# Squirco_Logic_v1_0.net
KiCad netlist of a schematic drawn in EAGLE
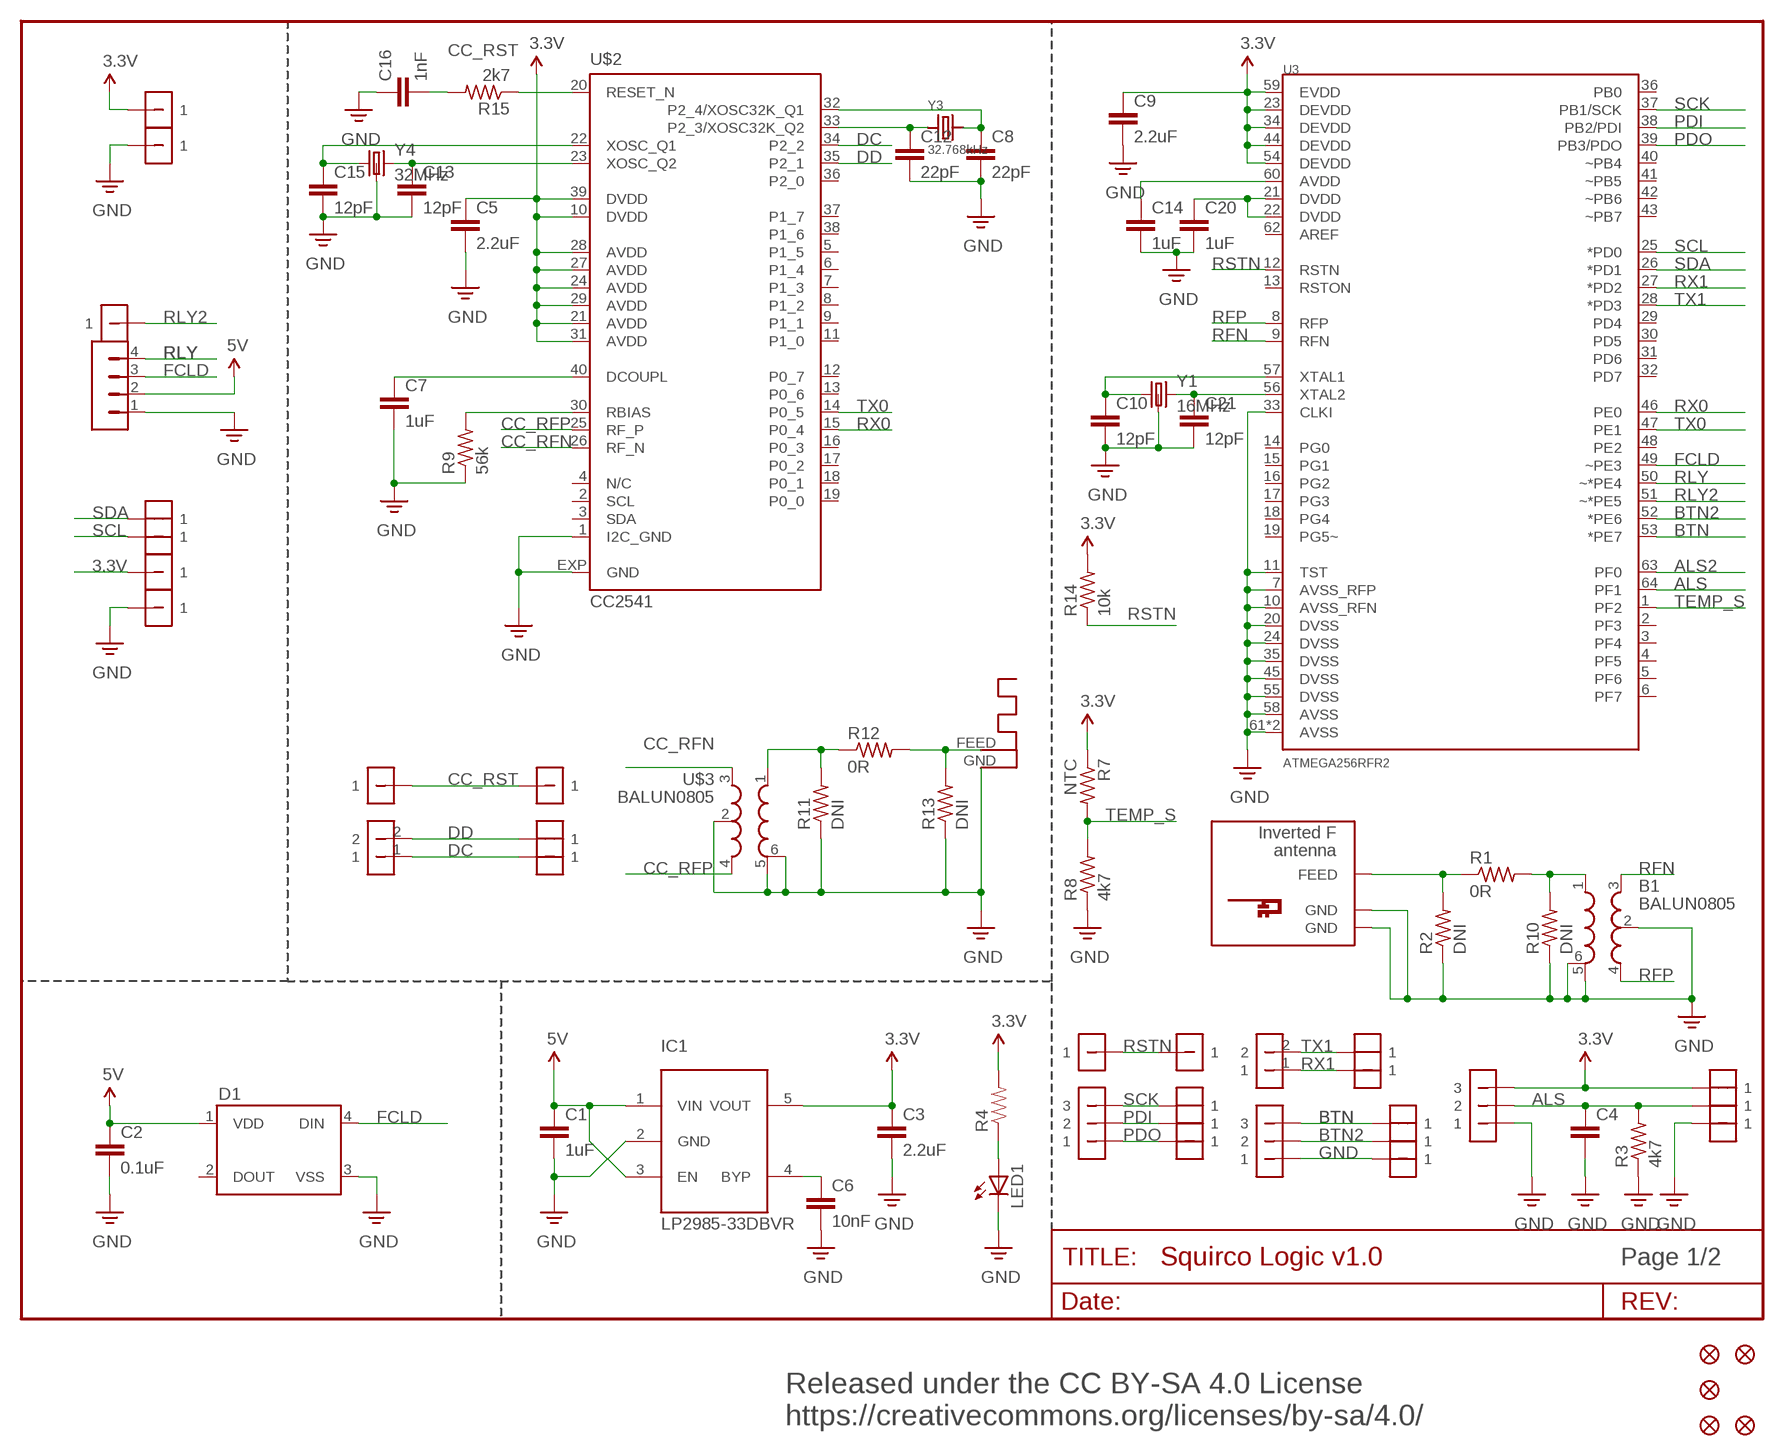
[diagram p0: schematic, sheet 1]

(export (version "E")
  (design (tool "Eeschema 10.0.6"))
  (components
    (comp (ref "ANT1")
      (value "ANTENNA")
      (footprint "eagle-import:RN-ANT")
      (libsource (lib "eagle-import") (part "ANTENNA"))
    )
    (comp (ref "B1")
      (value "BALUN0805")
      (footprint "eagle-import:BALUN-2-4GHZ")
      (libsource (lib "eagle-import") (part "BALUN0805"))
    )
    (comp (ref "C1")
      (value "1uF")
      (footprint "eagle-import:0603-CAP")
      (libsource (lib "eagle-import") (part "CAP0603-CAP"))
    )
    (comp (ref "C2")
      (value "0.1uF")
      (footprint "eagle-import:0603-CAP")
      (libsource (lib "eagle-import") (part "CAP0603-CAP"))
    )
    (comp (ref "C3")
      (value "2.2uF")
      (footprint "eagle-import:0603-CAP")
      (libsource (lib "eagle-import") (part "CAP0603-CAP"))
    )
    (comp (ref "C4")
      (value "CAP0603-CAP")
      (footprint "eagle-import:0603-CAP")
      (libsource (lib "eagle-import") (part "CAP0603-CAP"))
    )
    (comp (ref "C5")
      (value "2.2uF")
      (footprint "eagle-import:0603-CAP")
      (libsource (lib "eagle-import") (part "CAP0603-CAP"))
    )
    (comp (ref "C6")
      (value "10nF")
      (footprint "eagle-import:0603-CAP")
      (libsource (lib "eagle-import") (part "CAP0603-CAP"))
    )
    (comp (ref "C7")
      (value "1uF")
      (footprint "eagle-import:0603-CAP")
      (libsource (lib "eagle-import") (part "CAP0603-CAP"))
    )
    (comp (ref "C8")
      (value "22pF")
      (footprint "eagle-import:0402-CAP")
      (libsource (lib "eagle-import") (part "CAP0402-CAP"))
    )
    (comp (ref "C9")
      (value "2.2uF")
      (footprint "eagle-import:0603-CAP")
      (libsource (lib "eagle-import") (part "CAP0603-CAP"))
    )
    (comp (ref "C10")
      (value "12pF")
      (footprint "eagle-import:0402-CAP")
      (libsource (lib "eagle-import") (part "CAP0402-CAP"))
    )
    (comp (ref "C12")
      (value "22pF")
      (footprint "eagle-import:0402-CAP")
      (libsource (lib "eagle-import") (part "CAP0402-CAP"))
    )
    (comp (ref "C13")
      (value "12pF")
      (footprint "eagle-import:0402-CAP")
      (libsource (lib "eagle-import") (part "CAP0402-CAP"))
    )
    (comp (ref "C14")
      (value "1uF")
      (footprint "eagle-import:0603-CAP")
      (libsource (lib "eagle-import") (part "CAP0603-CAP"))
    )
    (comp (ref "C15")
      (value "12pF")
      (footprint "eagle-import:0402-CAP")
      (libsource (lib "eagle-import") (part "CAP0402-CAP"))
    )
    (comp (ref "C16")
      (value "1nF")
      (footprint "eagle-import:0603-CAP")
      (libsource (lib "eagle-import") (part "CAP0603-CAP"))
    )
    (comp (ref "C20")
      (value "1uF")
      (footprint "eagle-import:0603-CAP")
      (libsource (lib "eagle-import") (part "CAP0603-CAP"))
    )
    (comp (ref "C21")
      (value "12pF")
      (footprint "eagle-import:0402-CAP")
      (libsource (lib "eagle-import") (part "CAP0402-CAP"))
    )
    (comp (ref "D1")
      (value "WS2812B")
      (footprint "eagle-import:WS2812B")
      (libsource (lib "eagle-import") (part "WS2812B"))
    )
    (comp (ref "FID1")
      (value "FIDUCIALUFIDUCIAL")
      (footprint "eagle-import:MICRO-FIDUCIAL")
      (libsource (lib "eagle-import") (part "FIDUCIALUFIDUCIAL"))
    )
    (comp (ref "FID2")
      (value "FIDUCIALUFIDUCIAL")
      (footprint "eagle-import:MICRO-FIDUCIAL")
      (libsource (lib "eagle-import") (part "FIDUCIALUFIDUCIAL"))
    )
    (comp (ref "FID3")
      (value "FIDUCIALUFIDUCIAL")
      (footprint "eagle-import:MICRO-FIDUCIAL")
      (libsource (lib "eagle-import") (part "FIDUCIALUFIDUCIAL"))
    )
    (comp (ref "FID5")
      (value "FIDUCIALUFIDUCIAL")
      (footprint "eagle-import:MICRO-FIDUCIAL")
      (libsource (lib "eagle-import") (part "FIDUCIALUFIDUCIAL"))
    )
    (comp (ref "FID6")
      (value "FIDUCIALUFIDUCIAL")
      (footprint "eagle-import:MICRO-FIDUCIAL")
      (libsource (lib "eagle-import") (part "FIDUCIALUFIDUCIAL"))
    )
    (comp (ref "IC1")
      (value "LP2985-33DBVR")
      (footprint "eagle-import:SOT23-5L")
      (libsource (lib "eagle-import") (part "LP298XS"))
    )
    (comp (ref "JP1")
      (value "M02")
      (footprint "eagle-import:M02")
      (libsource (lib "eagle-import") (part "M02"))
    )
    (comp (ref "LED1")
      (value "LEDCHIP-LED0805")
      (footprint "eagle-import:CHIP-LED0805")
      (libsource (lib "eagle-import") (part "LEDCHIP-LED0805"))
    )
    (comp (ref "R1")
      (value "0R")
      (footprint "eagle-import:R0402")
      (libsource (lib "eagle-import") (part "R-US_R0402"))
    )
    (comp (ref "R2")
      (value "DNI")
      (footprint "eagle-import:R0402")
      (libsource (lib "eagle-import") (part "R-US_R0402"))
    )
    (comp (ref "R3")
      (value "4k7")
      (footprint "eagle-import:R0603")
      (libsource (lib "eagle-import") (part "R-US_R0603"))
    )
    (comp (ref "R4")
      (value "RESISTOR0603")
      (footprint "eagle-import:0603-RES")
      (libsource (lib "eagle-import") (part "RESISTOR0603"))
    )
    (comp (ref "R7")
      (value "NTC")
      (footprint "eagle-import:R0402")
      (libsource (lib "eagle-import") (part "R-US_R0402"))
    )
    (comp (ref "R8")
      (value "4k7")
      (footprint "eagle-import:R0603")
      (libsource (lib "eagle-import") (part "R-US_R0603"))
    )
    (comp (ref "R9")
      (value "56k")
      (footprint "eagle-import:R0603")
      (libsource (lib "eagle-import") (part "R-US_R0603"))
    )
    (comp (ref "R10")
      (value "DNI")
      (footprint "eagle-import:R0402")
      (libsource (lib "eagle-import") (part "R-US_R0402"))
    )
    (comp (ref "R11")
      (value "DNI")
      (footprint "eagle-import:R0402")
      (libsource (lib "eagle-import") (part "R-US_R0402"))
    )
    (comp (ref "R12")
      (value "0R")
      (footprint "eagle-import:R0402")
      (libsource (lib "eagle-import") (part "R-US_R0402"))
    )
    (comp (ref "R13")
      (value "DNI")
      (footprint "eagle-import:R0402")
      (libsource (lib "eagle-import") (part "R-US_R0402"))
    )
    (comp (ref "R14")
      (value "10k")
      (footprint "eagle-import:R0603")
      (libsource (lib "eagle-import") (part "R-US_R0603"))
    )
    (comp (ref "R15")
      (value "2k7")
      (footprint "eagle-import:R0603")
      (libsource (lib "eagle-import") (part "R-US_R0603"))
    )
    (comp (ref "U$1")
      (value "INVERTED_F_ANTENNA+5")
      (footprint "eagle-import:DN007+5")
      (libsource (lib "eagle-import") (part "INVERTED_F_ANTENNA+5"))
    )
    (comp (ref "U$2")
      (value "CC2541")
      (footprint "eagle-import:RHA_S-PVQFN-N40")
      (libsource (lib "eagle-import") (part "CC2541"))
    )
    (comp (ref "U$3")
      (value "BALUN0805")
      (footprint "eagle-import:BALUN-2-4GHZ")
      (libsource (lib "eagle-import") (part "BALUN0805"))
    )
    (comp (ref "U$4")
      (value "M03")
      (footprint "eagle-import:M03")
      (libsource (lib "eagle-import") (part "M03"))
    )
    (comp (ref "U$5")
      (value "S04-4MM")
      (footprint "eagle-import:S04-4MM")
      (libsource (lib "eagle-import") (part "S04-4MM"))
    )
    (comp (ref "U$6")
      (value "M03")
      (footprint "eagle-import:M03")
      (libsource (lib "eagle-import") (part "M03"))
    )
    (comp (ref "U$7")
      (value "M01")
      (footprint "eagle-import:M01")
      (libsource (lib "eagle-import") (part "M01"))
    )
    (comp (ref "U$8")
      (value "M01")
      (footprint "eagle-import:M01")
      (libsource (lib "eagle-import") (part "M01"))
    )
    (comp (ref "U$9")
      (value "M02")
      (footprint "eagle-import:M02")
      (libsource (lib "eagle-import") (part "M02"))
    )
    (comp (ref "U$10")
      (value "S01C-4MM")
      (footprint "eagle-import:S01C-4MM")
      (libsource (lib "eagle-import") (part "S01C-4MM"))
    )
    (comp (ref "U$11")
      (value "S01C-4MM")
      (footprint "eagle-import:S01C-4MM")
      (libsource (lib "eagle-import") (part "S01C-4MM"))
    )
    (comp (ref "U$12")
      (value "S01C-4MM")
      (footprint "eagle-import:S01C-4MM")
      (libsource (lib "eagle-import") (part "S01C-4MM"))
    )
    (comp (ref "U$13")
      (value "S01C-4MM")
      (footprint "eagle-import:S01C-4MM")
      (libsource (lib "eagle-import") (part "S01C-4MM"))
    )
    (comp (ref "U$14")
      (value "S01C-4MM")
      (footprint "eagle-import:S01C-4MM")
      (libsource (lib "eagle-import") (part "S01C-4MM"))
    )
    (comp (ref "U$15")
      (value "S01C-4MM")
      (footprint "eagle-import:S01C-4MM")
      (libsource (lib "eagle-import") (part "S01C-4MM"))
    )
    (comp (ref "U$16")
      (value "S01C-4MM")
      (footprint "eagle-import:S01C-4MM")
      (libsource (lib "eagle-import") (part "S01C-4MM"))
    )
    (comp (ref "U$17")
      (value "S01C-4MM")
      (footprint "eagle-import:S01C-4MM")
      (libsource (lib "eagle-import") (part "S01C-4MM"))
    )
    (comp (ref "U$18")
      (value "S01C-4MM")
      (footprint "eagle-import:S01C-4MM")
      (libsource (lib "eagle-import") (part "S01C-4MM"))
    )
    (comp (ref "U$19")
      (value "S01C-4MM")
      (footprint "eagle-import:S01C-4MM")
      (libsource (lib "eagle-import") (part "S01C-4MM"))
    )
    (comp (ref "U$20")
      (value "S01C-4MM")
      (footprint "eagle-import:S01C-4MM")
      (libsource (lib "eagle-import") (part "S01C-4MM"))
    )
    (comp (ref "U$21")
      (value "S01C-4MM")
      (footprint "eagle-import:S01C-4MM")
      (libsource (lib "eagle-import") (part "S01C-4MM"))
    )
    (comp (ref "U$22")
      (value "S01C-4MM")
      (footprint "eagle-import:S01C-4MM")
      (libsource (lib "eagle-import") (part "S01C-4MM"))
    )
    (comp (ref "U$23")
      (value "S01C-4MM")
      (footprint "eagle-import:S01C-4MM")
      (libsource (lib "eagle-import") (part "S01C-4MM"))
    )
    (comp (ref "U$24")
      (value "S01C-4MM")
      (footprint "eagle-import:S01C-4MM")
      (libsource (lib "eagle-import") (part "S01C-4MM"))
    )
    (comp (ref "U$25")
      (value "M03")
      (footprint "eagle-import:M03")
      (libsource (lib "eagle-import") (part "M03"))
    )
    (comp (ref "U$26")
      (value "S01C-4MM")
      (footprint "eagle-import:S01C-4MM")
      (libsource (lib "eagle-import") (part "S01C-4MM"))
    )
    (comp (ref "U$27")
      (value "S01C-4MM")
      (footprint "eagle-import:S01C-4MM")
      (libsource (lib "eagle-import") (part "S01C-4MM"))
    )
    (comp (ref "U$30")
      (value "S01C-4MM")
      (footprint "eagle-import:S01C-4MM")
      (libsource (lib "eagle-import") (part "S01C-4MM"))
    )
    (comp (ref "U$31")
      (value "S01C-4MM")
      (footprint "eagle-import:S01C-4MM")
      (libsource (lib "eagle-import") (part "S01C-4MM"))
    )
    (comp (ref "U$32")
      (value "S01-4MM")
      (footprint "eagle-import:S01-4MM")
      (libsource (lib "eagle-import") (part "S01-4MM"))
    )
    (comp (ref "U$33")
      (value "S01-4MM")
      (footprint "eagle-import:S01-4MM")
      (libsource (lib "eagle-import") (part "S01-4MM"))
    )
    (comp (ref "U$34")
      (value "S01C-4MM")
      (footprint "eagle-import:S01C-4MM")
      (libsource (lib "eagle-import") (part "S01C-4MM"))
    )
    (comp (ref "U3")
      (value "ATMEGA256RFR2")
      (footprint "eagle-import:QFN-64")
      (libsource (lib "eagle-import") (part "ATMEGA256RFR2"))
    )
    (comp (ref "Y1")
      (value "16MHz")
      (footprint "eagle-import:CRYSTAL-SMD-2.5X2-ABM10")
      (libsource (lib "eagle-import") (part "CRYSTALABM10"))
    )
    (comp (ref "Y3")
      (value "32.768kHz")
      (footprint "eagle-import:ABS07")
      (libsource (lib "eagle-import") (part "CRYSTAL.ABS07"))
    )
    (comp (ref "Y4")
      (value "32MHz")
      (footprint "eagle-import:CRYSTAL-SMD-2.5X2-ABM10")
      (libsource (lib "eagle-import") (part "CRYSTALABM10"))
    )
  )
  (nets
    (net (code "1") (name "/ALS") (class "Default")
      (node (ref "C4") (pin "1") (pinfunction "1_1") (pintype "passive"))
      (node (ref "R3") (pin "2") (pinfunction "2_2") (pintype "passive"))
      (node (ref "U$25") (pin "2") (pinfunction "2_2") (pintype "bidirectional"))
      (node (ref "U$31") (pin "P$1") (pinfunction "1_P$1") (pintype "bidirectional"))
      (node (ref "U3") (pin "64") (pinfunction "PF1_64") (pintype "bidirectional"))
    )
    (net (code "2") (name "/ALS2") (class "Default")
      (node (ref "U3") (pin "63") (pinfunction "PF0_63") (pintype "bidirectional"))
    )
    (net (code "3") (name "/BTN") (class "Default")
      (node (ref "U$22") (pin "P$1") (pinfunction "1_P$1") (pintype "bidirectional"))
      (node (ref "U$6") (pin "3") (pinfunction "3_3") (pintype "bidirectional"))
      (node (ref "U3") (pin "53") (pinfunction "*PE7_53") (pintype "bidirectional"))
    )
    (net (code "4") (name "/BTN2") (class "Default")
      (node (ref "U$23") (pin "P$1") (pinfunction "1_P$1") (pintype "bidirectional"))
      (node (ref "U$6") (pin "2") (pinfunction "2_2") (pintype "bidirectional"))
      (node (ref "U3") (pin "52") (pinfunction "*PE6_52") (pintype "bidirectional"))
    )
    (net (code "5") (name "/CC_RFN") (class "Default")
      (node (ref "U$2") (pin "26") (pinfunction "RF_N_26") (pintype "bidirectional"))
      (node (ref "U$3") (pin "3") (pinfunction "3_3") (pintype "bidirectional"))
    )
    (net (code "6") (name "/CC_RFP") (class "Default")
      (node (ref "U$2") (pin "25") (pinfunction "RF_P_25") (pintype "bidirectional"))
      (node (ref "U$3") (pin "4") (pinfunction "4_4") (pintype "bidirectional"))
    )
    (net (code "7") (name "/CC_RST") (class "Default")
      (node (ref "C16") (pin "2") (pinfunction "2_2") (pintype "passive"))
      (node (ref "R15") (pin "2") (pinfunction "2_2") (pintype "passive"))
      (node (ref "U$17") (pin "P$1") (pinfunction "1_P$1") (pintype "bidirectional"))
      (node (ref "U$8") (pin "1") (pinfunction "1_1") (pintype "bidirectional"))
    )
    (net (code "8") (name "/DC") (class "Default")
      (node (ref "U$19") (pin "P$1") (pinfunction "1_P$1") (pintype "bidirectional"))
      (node (ref "U$2") (pin "34") (pinfunction "P2_2_34") (pintype "bidirectional"))
      (node (ref "U$9") (pin "1") (pinfunction "1_1") (pintype "bidirectional"))
    )
    (net (code "9") (name "/DD") (class "Default")
      (node (ref "U$18") (pin "P$1") (pinfunction "1_P$1") (pintype "bidirectional"))
      (node (ref "U$2") (pin "35") (pinfunction "P2_1_35") (pintype "bidirectional"))
      (node (ref "U$9") (pin "2") (pinfunction "2_2") (pintype "bidirectional"))
    )
    (net (code "10") (name "/FCLD") (class "Default")
      (node (ref "D1") (pin "4") (pinfunction "DIN_4") (pintype "input"))
      (node (ref "U$5") (pin "3") (pinfunction "3_3") (pintype "bidirectional"))
      (node (ref "U3") (pin "49") (pinfunction "~{PE3}_49") (pintype "bidirectional"))
    )
    (net (code "11") (name "/N{slash}C") (class "Default")
      (node (ref "U$2") (pin "4") (pinfunction "N/C_4") (pintype "power_in"))
    )
    (net (code "12") (name "/PDI") (class "Default")
      (node (ref "U$13") (pin "P$1") (pinfunction "1_P$1") (pintype "bidirectional"))
      (node (ref "U$4") (pin "2") (pinfunction "2_2") (pintype "bidirectional"))
      (node (ref "U3") (pin "38") (pinfunction "PB2/PDI_38") (pintype "bidirectional"))
    )
    (net (code "13") (name "/PDO") (class "Default")
      (node (ref "U$14") (pin "P$1") (pinfunction "1_P$1") (pintype "bidirectional"))
      (node (ref "U$4") (pin "1") (pinfunction "1_1") (pintype "bidirectional"))
      (node (ref "U3") (pin "39") (pinfunction "PB3/PDO_39") (pintype "bidirectional"))
    )
    (net (code "14") (name "/RFN") (class "Default")
      (node (ref "B1") (pin "3") (pinfunction "3_3") (pintype "bidirectional"))
      (node (ref "U3") (pin "9") (pinfunction "RFN_9") (pintype "bidirectional"))
    )
    (net (code "15") (name "/RFP") (class "Default")
      (node (ref "B1") (pin "4") (pinfunction "4_4") (pintype "bidirectional"))
      (node (ref "U3") (pin "8") (pinfunction "RFP_8") (pintype "bidirectional"))
    )
    (net (code "16") (name "/RLY") (class "Default")
      (node (ref "U$5") (pin "4") (pinfunction "4_4") (pintype "bidirectional"))
      (node (ref "U3") (pin "50") (pinfunction "~{*PE4}_50") (pintype "bidirectional"))
    )
    (net (code "17") (name "/RLY2") (class "Default")
      (node (ref "U$34") (pin "P$1") (pinfunction "1_P$1") (pintype "bidirectional"))
      (node (ref "U3") (pin "51") (pinfunction "~{*PE5}_51") (pintype "bidirectional"))
    )
    (net (code "18") (name "/RSTN") (class "Default")
      (node (ref "R14") (pin "1") (pinfunction "1_1") (pintype "passive"))
      (node (ref "U$11") (pin "P$1") (pinfunction "1_P$1") (pintype "bidirectional"))
      (node (ref "U$7") (pin "1") (pinfunction "1_1") (pintype "bidirectional"))
      (node (ref "U3") (pin "12") (pinfunction "RSTN_12") (pintype "bidirectional"))
    )
    (net (code "19") (name "/RX0") (class "Default")
      (node (ref "U$2") (pin "15") (pinfunction "P0_4_15") (pintype "bidirectional"))
      (node (ref "U3") (pin "46") (pinfunction "PE0_46") (pintype "bidirectional"))
    )
    (net (code "20") (name "/RX1") (class "Default")
      (node (ref "JP1") (pin "1") (pinfunction "1_1") (pintype "bidirectional"))
      (node (ref "U$16") (pin "P$1") (pinfunction "1_P$1") (pintype "bidirectional"))
      (node (ref "U3") (pin "27") (pinfunction "*PD2_27") (pintype "bidirectional"))
    )
    (net (code "21") (name "/SCK") (class "Default")
      (node (ref "U$12") (pin "P$1") (pinfunction "1_P$1") (pintype "bidirectional"))
      (node (ref "U$4") (pin "3") (pinfunction "3_3") (pintype "bidirectional"))
      (node (ref "U3") (pin "37") (pinfunction "PB1/SCK_37") (pintype "bidirectional"))
    )
    (net (code "22") (name "/SCL") (class "Default")
      (node (ref "U$24") (pin "P$1") (pinfunction "1_P$1") (pintype "bidirectional"))
      (node (ref "U3") (pin "25") (pinfunction "*PD0_25") (pintype "bidirectional"))
    )
    (net (code "23") (name "/SDA") (class "Default")
      (node (ref "U$10") (pin "P$1") (pinfunction "1_P$1") (pintype "bidirectional"))
      (node (ref "U3") (pin "26") (pinfunction "*PD1_26") (pintype "bidirectional"))
    )
    (net (code "24") (name "/TEMP_S") (class "Default")
      (node (ref "R7") (pin "2") (pinfunction "2_2") (pintype "passive"))
      (node (ref "R8") (pin "2") (pinfunction "2_2") (pintype "passive"))
      (node (ref "U3") (pin "1") (pinfunction "PF2_1") (pintype "bidirectional"))
    )
    (net (code "25") (name "/TX0") (class "Default")
      (node (ref "U$2") (pin "14") (pinfunction "P0_5_14") (pintype "bidirectional"))
      (node (ref "U3") (pin "47") (pinfunction "PE1_47") (pintype "bidirectional"))
    )
    (net (code "26") (name "/TX1") (class "Default")
      (node (ref "JP1") (pin "2") (pinfunction "2_2") (pintype "bidirectional"))
      (node (ref "U$15") (pin "P$1") (pinfunction "1_P$1") (pintype "bidirectional"))
      (node (ref "U3") (pin "28") (pinfunction "*PD3_28") (pintype "bidirectional"))
    )
    (net (code "27") (name "3.3V") (class "Default")
      (node (ref "C3") (pin "1") (pinfunction "1_1") (pintype "passive"))
      (node (ref "C5") (pin "1") (pinfunction "1_1") (pintype "passive"))
      (node (ref "C9") (pin "1") (pinfunction "1_1") (pintype "passive"))
      (node (ref "IC1") (pin "5") (pinfunction "VOUT_5") (pintype "bidirectional"))
      (node (ref "R14") (pin "2") (pinfunction "2_2") (pintype "passive"))
      (node (ref "R4") (pin "2") (pinfunction "2_2") (pintype "passive"))
      (node (ref "R7") (pin "1") (pinfunction "1_1") (pintype "passive"))
      (node (ref "U$2") (pin "10") (pinfunction "DVDD_10") (pintype "power_in"))
      (node (ref "U$2") (pin "21") (pinfunction "AVDD_21") (pintype "power_in"))
      (node (ref "U$2") (pin "24") (pinfunction "AVDD_24") (pintype "power_in"))
      (node (ref "U$2") (pin "27") (pinfunction "AVDD_27") (pintype "power_in"))
      (node (ref "U$2") (pin "28") (pinfunction "AVDD_28") (pintype "power_in"))
      (node (ref "U$2") (pin "29") (pinfunction "AVDD_29") (pintype "power_in"))
      (node (ref "U$2") (pin "31") (pinfunction "AVDD_31") (pintype "power_in"))
      (node (ref "U$2") (pin "39") (pinfunction "DVDD_39") (pintype "power_in"))
      (node (ref "U$20") (pin "P$1") (pinfunction "1_P$1") (pintype "bidirectional"))
      (node (ref "U$25") (pin "3") (pinfunction "3_3") (pintype "bidirectional"))
      (node (ref "U$26") (pin "P$1") (pinfunction "1_P$1") (pintype "bidirectional"))
      (node (ref "U$30") (pin "P$1") (pinfunction "1_P$1") (pintype "bidirectional"))
      (node (ref "U3") (pin "23") (pinfunction "DEVDD_23") (pintype "bidirectional"))
      (node (ref "U3") (pin "34") (pinfunction "DEVDD_34") (pintype "bidirectional"))
      (node (ref "U3") (pin "44") (pinfunction "DEVDD_44") (pintype "bidirectional"))
      (node (ref "U3") (pin "54") (pinfunction "DEVDD_54") (pintype "bidirectional"))
      (node (ref "U3") (pin "59") (pinfunction "EVDD_59") (pintype "bidirectional"))
    )
    (net (code "28") (name "5V") (class "Default")
      (node (ref "C1") (pin "1") (pinfunction "1_1") (pintype "passive"))
      (node (ref "C2") (pin "1") (pinfunction "1_1") (pintype "passive"))
      (node (ref "D1") (pin "1") (pinfunction "VDD_1") (pintype "power_in"))
      (node (ref "IC1") (pin "1") (pinfunction "VIN_1") (pintype "bidirectional"))
      (node (ref "IC1") (pin "3") (pinfunction "EN_3") (pintype "bidirectional"))
      (node (ref "U$5") (pin "2") (pinfunction "2_2") (pintype "bidirectional"))
    )
    (net (code "29") (name "GND") (class "Default")
      (node (ref "ANT1") (pin "GND") (pinfunction "GND_GND") (pintype "passive"))
      (node (ref "B1") (pin "2") (pinfunction "2_2") (pintype "bidirectional"))
      (node (ref "B1") (pin "5") (pinfunction "5_5") (pintype "bidirectional"))
      (node (ref "B1") (pin "6") (pinfunction "6_6") (pintype "bidirectional"))
      (node (ref "C1") (pin "2") (pinfunction "2_2") (pintype "passive"))
      (node (ref "C10") (pin "2") (pinfunction "2_2") (pintype "passive"))
      (node (ref "C12") (pin "2") (pinfunction "2_2") (pintype "passive"))
      (node (ref "C13") (pin "2") (pinfunction "2_2") (pintype "passive"))
      (node (ref "C14") (pin "2") (pinfunction "2_2") (pintype "passive"))
      (node (ref "C15") (pin "2") (pinfunction "2_2") (pintype "passive"))
      (node (ref "C16") (pin "1") (pinfunction "1_1") (pintype "passive"))
      (node (ref "C2") (pin "2") (pinfunction "2_2") (pintype "passive"))
      (node (ref "C20") (pin "2") (pinfunction "2_2") (pintype "passive"))
      (node (ref "C21") (pin "2") (pinfunction "2_2") (pintype "passive"))
      (node (ref "C3") (pin "2") (pinfunction "2_2") (pintype "passive"))
      (node (ref "C4") (pin "2") (pinfunction "2_2") (pintype "passive"))
      (node (ref "C5") (pin "2") (pinfunction "2_2") (pintype "passive"))
      (node (ref "C6") (pin "2") (pinfunction "2_2") (pintype "passive"))
      (node (ref "C7") (pin "2") (pinfunction "2_2") (pintype "passive"))
      (node (ref "C8") (pin "2") (pinfunction "2_2") (pintype "passive"))
      (node (ref "C9") (pin "2") (pinfunction "2_2") (pintype "passive"))
      (node (ref "D1") (pin "3") (pinfunction "VSS_3") (pintype "power_in"))
      (node (ref "IC1") (pin "2") (pinfunction "GND_2") (pintype "bidirectional"))
      (node (ref "LED1") (pin "C") (pinfunction "C_C") (pintype "passive"))
      (node (ref "R10") (pin "1") (pinfunction "1_1") (pintype "passive"))
      (node (ref "R11") (pin "1") (pinfunction "1_1") (pintype "passive"))
      (node (ref "R13") (pin "1") (pinfunction "1_1") (pintype "passive"))
      (node (ref "R2") (pin "1") (pinfunction "1_1") (pintype "passive"))
      (node (ref "R3") (pin "1") (pinfunction "1_1") (pintype "passive"))
      (node (ref "R8") (pin "1") (pinfunction "1_1") (pintype "passive"))
      (node (ref "R9") (pin "1") (pinfunction "1_1") (pintype "passive"))
      (node (ref "U$1") (pin "GND") (pinfunction "GND_GND") (pintype "bidirectional"))
      (node (ref "U$1") (pin "GND@1") (pinfunction "GND_GND@1") (pintype "bidirectional"))
      (node (ref "U$2") (pin "1") (pinfunction "I2C_GND_1") (pintype "power_in"))
      (node (ref "U$2") (pin "EXP") (pinfunction "GND_EXP") (pintype "passive"))
      (node (ref "U$21") (pin "P$1") (pinfunction "1_P$1") (pintype "bidirectional"))
      (node (ref "U$25") (pin "1") (pinfunction "1_1") (pintype "bidirectional"))
      (node (ref "U$27") (pin "P$1") (pinfunction "1_P$1") (pintype "bidirectional"))
      (node (ref "U$3") (pin "2") (pinfunction "2_2") (pintype "bidirectional"))
      (node (ref "U$3") (pin "5") (pinfunction "5_5") (pintype "bidirectional"))
      (node (ref "U$3") (pin "6") (pinfunction "6_6") (pintype "bidirectional"))
      (node (ref "U$32") (pin "P$1") (pinfunction "1_P$1") (pintype "bidirectional"))
      (node (ref "U$33") (pin "P$1") (pinfunction "1_P$1") (pintype "bidirectional"))
      (node (ref "U$5") (pin "1") (pinfunction "1_1") (pintype "bidirectional"))
      (node (ref "U$6") (pin "1") (pinfunction "1_1") (pintype "bidirectional"))
      (node (ref "U3") (pin "10") (pinfunction "AVSS_RFN_10") (pintype "bidirectional"))
      (node (ref "U3") (pin "11") (pinfunction "TST_11") (pintype "bidirectional"))
      (node (ref "U3") (pin "20") (pinfunction "DVSS_20") (pintype "bidirectional"))
      (node (ref "U3") (pin "24") (pinfunction "DVSS_24") (pintype "bidirectional"))
      (node (ref "U3") (pin "33") (pinfunction "CLKI_33") (pintype "bidirectional"))
      (node (ref "U3") (pin "35") (pinfunction "DVSS_35") (pintype "bidirectional"))
      (node (ref "U3") (pin "45") (pinfunction "DVSS_45") (pintype "bidirectional"))
      (node (ref "U3") (pin "55") (pinfunction "DVSS_55") (pintype "bidirectional"))
      (node (ref "U3") (pin "58") (pinfunction "AVSS_58") (pintype "bidirectional"))
      (node (ref "U3") (pin "61") (pinfunction "AVSS_61") (pintype "bidirectional"))
      (node (ref "U3") (pin "7") (pinfunction "AVSS_RFP_7") (pintype "bidirectional"))
      (node (ref "U3") (pin "PADDLE") (pinfunction "AVSS_PADDLE") (pintype "bidirectional"))
      (node (ref "Y1") (pin "P$2") (pinfunction "GND_P$2") (pintype "bidirectional"))
      (node (ref "Y1") (pin "P$4") (pinfunction "GND_P$4") (pintype "bidirectional"))
      (node (ref "Y4") (pin "P$2") (pinfunction "GND_P$2") (pintype "bidirectional"))
      (node (ref "Y4") (pin "P$4") (pinfunction "GND_P$4") (pintype "bidirectional"))
    )
    (net (code "30") (name "Net-(ANT1-PadFEED)") (class "Default")
      (node (ref "ANT1") (pin "FEED") (pinfunction "FEED_FEED") (pintype "passive"))
      (node (ref "R12") (pin "2") (pinfunction "2_2") (pintype "passive"))
      (node (ref "R13") (pin "2") (pinfunction "2_2") (pintype "passive"))
    )
    (net (code "31") (name "Net-(B1-Pad1)") (class "Default")
      (node (ref "B1") (pin "1") (pinfunction "1_1") (pintype "bidirectional"))
      (node (ref "R1") (pin "2") (pinfunction "2_2") (pintype "passive"))
      (node (ref "R10") (pin "2") (pinfunction "2_2") (pintype "passive"))
    )
    (net (code "32") (name "Net-(C20-Pad1)") (class "Default")
      (node (ref "C20") (pin "1") (pinfunction "1_1") (pintype "passive"))
      (node (ref "U3") (pin "21") (pinfunction "DVDD_21") (pintype "bidirectional"))
      (node (ref "U3") (pin "22") (pinfunction "DVDD_22") (pintype "bidirectional"))
    )
    (net (code "33") (name "Net-(IC1-BYP)") (class "Default")
      (node (ref "C6") (pin "1") (pinfunction "1_1") (pintype "passive"))
      (node (ref "IC1") (pin "4") (pinfunction "BYP_4") (pintype "bidirectional"))
    )
    (net (code "34") (name "Net-(LED1-PadA)") (class "Default")
      (node (ref "LED1") (pin "A") (pinfunction "A_A") (pintype "passive"))
      (node (ref "R4") (pin "1") (pinfunction "1_1") (pintype "passive"))
    )
    (net (code "35") (name "Net-(R1-Pad1)") (class "Default")
      (node (ref "R1") (pin "1") (pinfunction "1_1") (pintype "passive"))
      (node (ref "R2") (pin "2") (pinfunction "2_2") (pintype "passive"))
      (node (ref "U$1") (pin "FEED") (pinfunction "FEED_FEED") (pintype "bidirectional"))
    )
    (net (code "36") (name "Net-(R11-Pad2)") (class "Default")
      (node (ref "R11") (pin "2") (pinfunction "2_2") (pintype "passive"))
      (node (ref "R12") (pin "1") (pinfunction "1_1") (pintype "passive"))
      (node (ref "U$3") (pin "1") (pinfunction "1_1") (pintype "bidirectional"))
    )
    (net (code "37") (name "Net-(U$2-DCOUPL)") (class "Default")
      (node (ref "C7") (pin "1") (pinfunction "1_1") (pintype "passive"))
      (node (ref "U$2") (pin "40") (pinfunction "DCOUPL_40") (pintype "power_in"))
    )
    (net (code "38") (name "Net-(U$2-P2_3{slash}XOSC32K_Q2)") (class "Default")
      (node (ref "C12") (pin "1") (pinfunction "1_1") (pintype "passive"))
      (node (ref "U$2") (pin "33") (pinfunction "P2_3/XOSC32K_Q2_33") (pintype "bidirectional"))
      (node (ref "Y3") (pin "1") (pinfunction "1_1") (pintype "passive"))
    )
    (net (code "39") (name "Net-(U$2-P2_4{slash}XOSC32K_Q1)") (class "Default")
      (node (ref "C8") (pin "1") (pinfunction "1_1") (pintype "passive"))
      (node (ref "U$2") (pin "32") (pinfunction "P2_4/XOSC32K_Q1_32") (pintype "bidirectional"))
      (node (ref "Y3") (pin "2") (pinfunction "2_2") (pintype "passive"))
    )
    (net (code "40") (name "Net-(U$2-RBIAS)") (class "Default")
      (node (ref "R9") (pin "2") (pinfunction "2_2") (pintype "passive"))
      (node (ref "U$2") (pin "30") (pinfunction "RBIAS_30") (pintype "bidirectional"))
    )
    (net (code "41") (name "Net-(U$2-RESET_N)") (class "Default")
      (node (ref "R15") (pin "1") (pinfunction "1_1") (pintype "passive"))
      (node (ref "U$2") (pin "20") (pinfunction "RESET_N_20") (pintype "input"))
    )
    (net (code "42") (name "Net-(U$2-XOSC_Q1)") (class "Default")
      (node (ref "C15") (pin "1") (pinfunction "1_1") (pintype "passive"))
      (node (ref "U$2") (pin "22") (pinfunction "XOSC_Q1_22") (pintype "bidirectional"))
      (node (ref "Y4") (pin "P$1") (pinfunction "1_P$1") (pintype "passive"))
    )
    (net (code "43") (name "Net-(U$2-XOSC_Q2)") (class "Default")
      (node (ref "C13") (pin "1") (pinfunction "1_1") (pintype "passive"))
      (node (ref "U$2") (pin "23") (pinfunction "XOSC_Q2_23") (pintype "bidirectional"))
      (node (ref "Y4") (pin "P$3") (pinfunction "2_P$3") (pintype "passive"))
    )
    (net (code "44") (name "Net-(U3-AVDD)") (class "Default")
      (node (ref "C14") (pin "1") (pinfunction "1_1") (pintype "passive"))
      (node (ref "U3") (pin "60") (pinfunction "AVDD_60") (pintype "bidirectional"))
    )
    (net (code "45") (name "Net-(U3-XTAL1)") (class "Default")
      (node (ref "C10") (pin "1") (pinfunction "1_1") (pintype "passive"))
      (node (ref "U3") (pin "57") (pinfunction "XTAL1_57") (pintype "bidirectional"))
      (node (ref "Y1") (pin "P$1") (pinfunction "1_P$1") (pintype "passive"))
    )
    (net (code "46") (name "Net-(U3-XTAL2)") (class "Default")
      (node (ref "C21") (pin "1") (pinfunction "1_1") (pintype "passive"))
      (node (ref "U3") (pin "56") (pinfunction "XTAL2_56") (pintype "bidirectional"))
      (node (ref "Y1") (pin "P$3") (pinfunction "2_P$3") (pintype "passive"))
    )
    (net (code "47") (name "unconnected-(D1-DOUT-Pad2)") (class "Default")
      (node (ref "D1") (pin "2") (pinfunction "DOUT_2") (pintype "output"))
    )
    (net (code "48") (name "unconnected-(U$2-P0_0-Pad19)") (class "Default")
      (node (ref "U$2") (pin "19") (pinfunction "P0_0_19") (pintype "bidirectional"))
    )
    (net (code "49") (name "unconnected-(U$2-P0_1-Pad18)") (class "Default")
      (node (ref "U$2") (pin "18") (pinfunction "P0_1_18") (pintype "bidirectional"))
    )
    (net (code "50") (name "unconnected-(U$2-P0_2-Pad17)") (class "Default")
      (node (ref "U$2") (pin "17") (pinfunction "P0_2_17") (pintype "bidirectional"))
    )
    (net (code "51") (name "unconnected-(U$2-P0_3-Pad16)") (class "Default")
      (node (ref "U$2") (pin "16") (pinfunction "P0_3_16") (pintype "bidirectional"))
    )
    (net (code "52") (name "unconnected-(U$2-P0_6-Pad13)") (class "Default")
      (node (ref "U$2") (pin "13") (pinfunction "P0_6_13") (pintype "bidirectional"))
    )
    (net (code "53") (name "unconnected-(U$2-P0_7-Pad12)") (class "Default")
      (node (ref "U$2") (pin "12") (pinfunction "P0_7_12") (pintype "bidirectional"))
    )
    (net (code "54") (name "unconnected-(U$2-P1_0-Pad11)") (class "Default")
      (node (ref "U$2") (pin "11") (pinfunction "P1_0_11") (pintype "bidirectional"))
    )
    (net (code "55") (name "unconnected-(U$2-P1_1-Pad9)") (class "Default")
      (node (ref "U$2") (pin "9") (pinfunction "P1_1_9") (pintype "bidirectional"))
    )
    (net (code "56") (name "unconnected-(U$2-P1_2-Pad8)") (class "Default")
      (node (ref "U$2") (pin "8") (pinfunction "P1_2_8") (pintype "bidirectional"))
    )
    (net (code "57") (name "unconnected-(U$2-P1_3-Pad7)") (class "Default")
      (node (ref "U$2") (pin "7") (pinfunction "P1_3_7") (pintype "bidirectional"))
    )
    (net (code "58") (name "unconnected-(U$2-P1_4-Pad6)") (class "Default")
      (node (ref "U$2") (pin "6") (pinfunction "P1_4_6") (pintype "bidirectional"))
    )
    (net (code "59") (name "unconnected-(U$2-P1_5-Pad5)") (class "Default")
      (node (ref "U$2") (pin "5") (pinfunction "P1_5_5") (pintype "bidirectional"))
    )
    (net (code "60") (name "unconnected-(U$2-P1_6-Pad38)") (class "Default")
      (node (ref "U$2") (pin "38") (pinfunction "P1_6_38") (pintype "bidirectional"))
    )
    (net (code "61") (name "unconnected-(U$2-P1_7-Pad37)") (class "Default")
      (node (ref "U$2") (pin "37") (pinfunction "P1_7_37") (pintype "bidirectional"))
    )
    (net (code "62") (name "unconnected-(U$2-P2_0-Pad36)") (class "Default")
      (node (ref "U$2") (pin "36") (pinfunction "P2_0_36") (pintype "bidirectional"))
    )
    (net (code "63") (name "unconnected-(U$2-SCL-Pad2)") (class "Default")
      (node (ref "U$2") (pin "2") (pinfunction "SCL_2") (pintype "bidirectional"))
    )
    (net (code "64") (name "unconnected-(U$2-SDA-Pad3)") (class "Default")
      (node (ref "U$2") (pin "3") (pinfunction "SDA_3") (pintype "bidirectional"))
    )
    (net (code "65") (name "unconnected-(U3-AREF-Pad62)") (class "Default")
      (node (ref "U3") (pin "62") (pinfunction "AREF_62") (pintype "bidirectional"))
    )
    (net (code "66") (name "unconnected-(U3-PB0-Pad36)") (class "Default")
      (node (ref "U3") (pin "36") (pinfunction "PB0_36") (pintype "bidirectional"))
    )
    (net (code "67") (name "unconnected-(U3-PD4-Pad29)") (class "Default")
      (node (ref "U3") (pin "29") (pinfunction "PD4_29") (pintype "bidirectional"))
    )
    (net (code "68") (name "unconnected-(U3-PD5-Pad30)") (class "Default")
      (node (ref "U3") (pin "30") (pinfunction "PD5_30") (pintype "bidirectional"))
    )
    (net (code "69") (name "unconnected-(U3-PD6-Pad31)") (class "Default")
      (node (ref "U3") (pin "31") (pinfunction "PD6_31") (pintype "bidirectional"))
    )
    (net (code "70") (name "unconnected-(U3-PD7-Pad32)") (class "Default")
      (node (ref "U3") (pin "32") (pinfunction "PD7_32") (pintype "bidirectional"))
    )
    (net (code "71") (name "unconnected-(U3-PE2-Pad48)") (class "Default")
      (node (ref "U3") (pin "48") (pinfunction "PE2_48") (pintype "bidirectional"))
    )
    (net (code "72") (name "unconnected-(U3-PF3-Pad2)") (class "Default")
      (node (ref "U3") (pin "2") (pinfunction "PF3_2") (pintype "bidirectional"))
    )
    (net (code "73") (name "unconnected-(U3-PF4-Pad3)") (class "Default")
      (node (ref "U3") (pin "3") (pinfunction "PF4_3") (pintype "bidirectional"))
    )
    (net (code "74") (name "unconnected-(U3-PF5-Pad4)") (class "Default")
      (node (ref "U3") (pin "4") (pinfunction "PF5_4") (pintype "bidirectional"))
    )
    (net (code "75") (name "unconnected-(U3-PF6-Pad5)") (class "Default")
      (node (ref "U3") (pin "5") (pinfunction "PF6_5") (pintype "bidirectional"))
    )
    (net (code "76") (name "unconnected-(U3-PF7-Pad6)") (class "Default")
      (node (ref "U3") (pin "6") (pinfunction "PF7_6") (pintype "bidirectional"))
    )
    (net (code "77") (name "unconnected-(U3-PG0-Pad14)") (class "Default")
      (node (ref "U3") (pin "14") (pinfunction "PG0_14") (pintype "bidirectional"))
    )
    (net (code "78") (name "unconnected-(U3-PG1-Pad15)") (class "Default")
      (node (ref "U3") (pin "15") (pinfunction "PG1_15") (pintype "bidirectional"))
    )
    (net (code "79") (name "unconnected-(U3-PG2-Pad16)") (class "Default")
      (node (ref "U3") (pin "16") (pinfunction "PG2_16") (pintype "bidirectional"))
    )
    (net (code "80") (name "unconnected-(U3-PG3-Pad17)") (class "Default")
      (node (ref "U3") (pin "17") (pinfunction "PG3_17") (pintype "bidirectional"))
    )
    (net (code "81") (name "unconnected-(U3-PG4-Pad18)") (class "Default")
      (node (ref "U3") (pin "18") (pinfunction "PG4_18") (pintype "bidirectional"))
    )
    (net (code "82") (name "unconnected-(U3-PG5~{}-Pad19)") (class "Default")
      (node (ref "U3") (pin "19") (pinfunction "PG5~{}_19") (pintype "bidirectional"))
    )
    (net (code "83") (name "unconnected-(U3-RSTON-Pad13)") (class "Default")
      (node (ref "U3") (pin "13") (pinfunction "RSTON_13") (pintype "bidirectional"))
    )
    (net (code "84") (name "unconnected-(U3-~{PB4}-Pad40)") (class "Default")
      (node (ref "U3") (pin "40") (pinfunction "~{PB4}_40") (pintype "bidirectional"))
    )
    (net (code "85") (name "unconnected-(U3-~{PB5}-Pad41)") (class "Default")
      (node (ref "U3") (pin "41") (pinfunction "~{PB5}_41") (pintype "bidirectional"))
    )
    (net (code "86") (name "unconnected-(U3-~{PB6}-Pad42)") (class "Default")
      (node (ref "U3") (pin "42") (pinfunction "~{PB6}_42") (pintype "bidirectional"))
    )
    (net (code "87") (name "unconnected-(U3-~{PB7}-Pad43)") (class "Default")
      (node (ref "U3") (pin "43") (pinfunction "~{PB7}_43") (pintype "bidirectional"))
    )
  )
)
